# 14_-RTC.net
KiCad netlist of a schematic drawn in Altium Designer
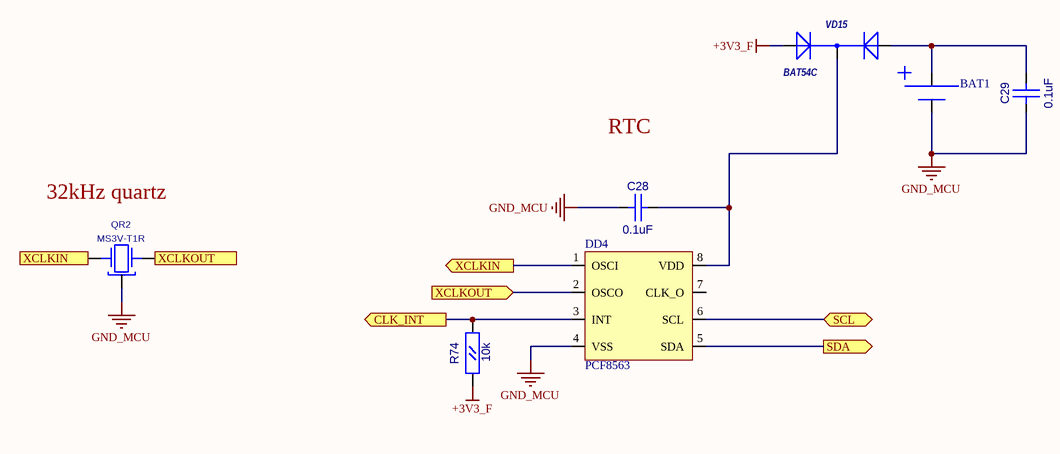
[diagram p0: [14]-RTC.SchDoc]

(export (version "E")
  (design (tool "Eeschema 10.0.6"))
  (components
    (comp (ref "BAT1")
      (value "CR2032-VBY4")
      (footprint "CR2032_ONBOARD")
      (libsource (lib "fizik_lib") (part "CR2032-VBY2"))
    )
    (comp (ref "C28")
      (value "0.1uF")
      (footprint "CC0603")
      (description "CC0603")
      (libsource (lib "gprs_modem_2") (part "CC0603"))
    )
    (comp (ref "C29")
      (value "0.1uF")
      (footprint "CC0603")
      (description "CC0603")
      (libsource (lib "gprs_modem_2") (part "CC0603"))
    )
    (comp (ref "DD4") (value "PCF8563") (footprint "SO-8") (libsource (lib "gprs_modem") (part "PCF8563")))
    (comp (ref "QR2")
      (value "MS3V-T1R")
      (footprint "MS3V-T1R")
      (description "CRYSTAL_32768 Hz")
      (libsource (lib "gprs_modem") (part "MS3V-T1R"))
    )
    (comp (ref "R74")
      (value "10k")
      (footprint "RC0603")
      (description "RC0603")
      (libsource (lib "fizik_lib") (part "RC0603"))
    )
    (comp (ref "VD15")
      (value "BAT54C")
      (footprint "SOT-23(123)")
      (libsource (lib "fizik_lib") (part "BAT54C"))
    )
  )
  (nets
    (net (code "1") (name "+3V3_F") (class "Default")
      (node (ref "R74") (pin "1") (pinfunction "A_1") (pintype "passive"))
      (node (ref "VD15") (pin "1") (pinfunction "A_1") (pintype "passive"))
    )
    (net (code "2") (name "/CLK_INT") (class "Default")
      (node (ref "DD4") (pin "3") (pinfunction "INT_3") (pintype "passive"))
      (node (ref "R74") (pin "2") (pinfunction "B_2") (pintype "passive"))
    )
    (net (code "3") (name "/SCL") (class "Default")
      (node (ref "DD4") (pin "6") (pinfunction "SCL_6") (pintype "passive"))
    )
    (net (code "4") (name "/SDA") (class "Default")
      (node (ref "DD4") (pin "5") (pinfunction "SDA_5") (pintype "passive"))
    )
    (net (code "5") (name "/XCLKIN") (class "Default")
      (node (ref "DD4") (pin "1") (pinfunction "OSCI_1") (pintype "passive"))
      (node (ref "QR2") (pin "2") (pinfunction "X2_2") (pintype "passive"))
    )
    (net (code "6") (name "/XCLKOUT") (class "Default")
      (node (ref "DD4") (pin "2") (pinfunction "OSCO_2") (pintype "passive"))
      (node (ref "QR2") (pin "1") (pinfunction "X1_1") (pintype "passive"))
    )
    (net (code "7") (name "GND_MCU") (class "Default")
      (node (ref "BAT1") (pin "1") (pintype "passive"))
      (node (ref "C28") (pin "1") (pinfunction "A_1") (pintype "passive"))
      (node (ref "C29") (pin "1") (pinfunction "A_1") (pintype "passive"))
      (node (ref "DD4") (pin "4") (pinfunction "VSS_4") (pintype "passive"))
      (node (ref "QR2") (pin "3") (pinfunction "3_3") (pintype "passive"))
    )
    (net (code "8") (name "Net-(C28-B)") (class "Default")
      (node (ref "C28") (pin "2") (pinfunction "B_2") (pintype "passive"))
      (node (ref "DD4") (pin "8") (pinfunction "VDD_8") (pintype "passive"))
      (node (ref "VD15") (pin "3") (pinfunction "K_3") (pintype "passive"))
    )
    (net (code "9") (name "Net-(C29-B)") (class "Default")
      (node (ref "BAT1") (pin "2") (pintype "passive"))
      (node (ref "C29") (pin "2") (pinfunction "B_2") (pintype "passive"))
      (node (ref "VD15") (pin "2") (pinfunction "A_2") (pintype "passive"))
    )
    (net (code "10") (name "unconnected-(DD4-CLK_O-Pad7)") (class "Default")
      (node (ref "DD4") (pin "7") (pinfunction "CLK_O_7") (pintype "passive"))
    )
  )
)
